# SCH.net
KiCad netlist of a schematic drawn in Altium Designer
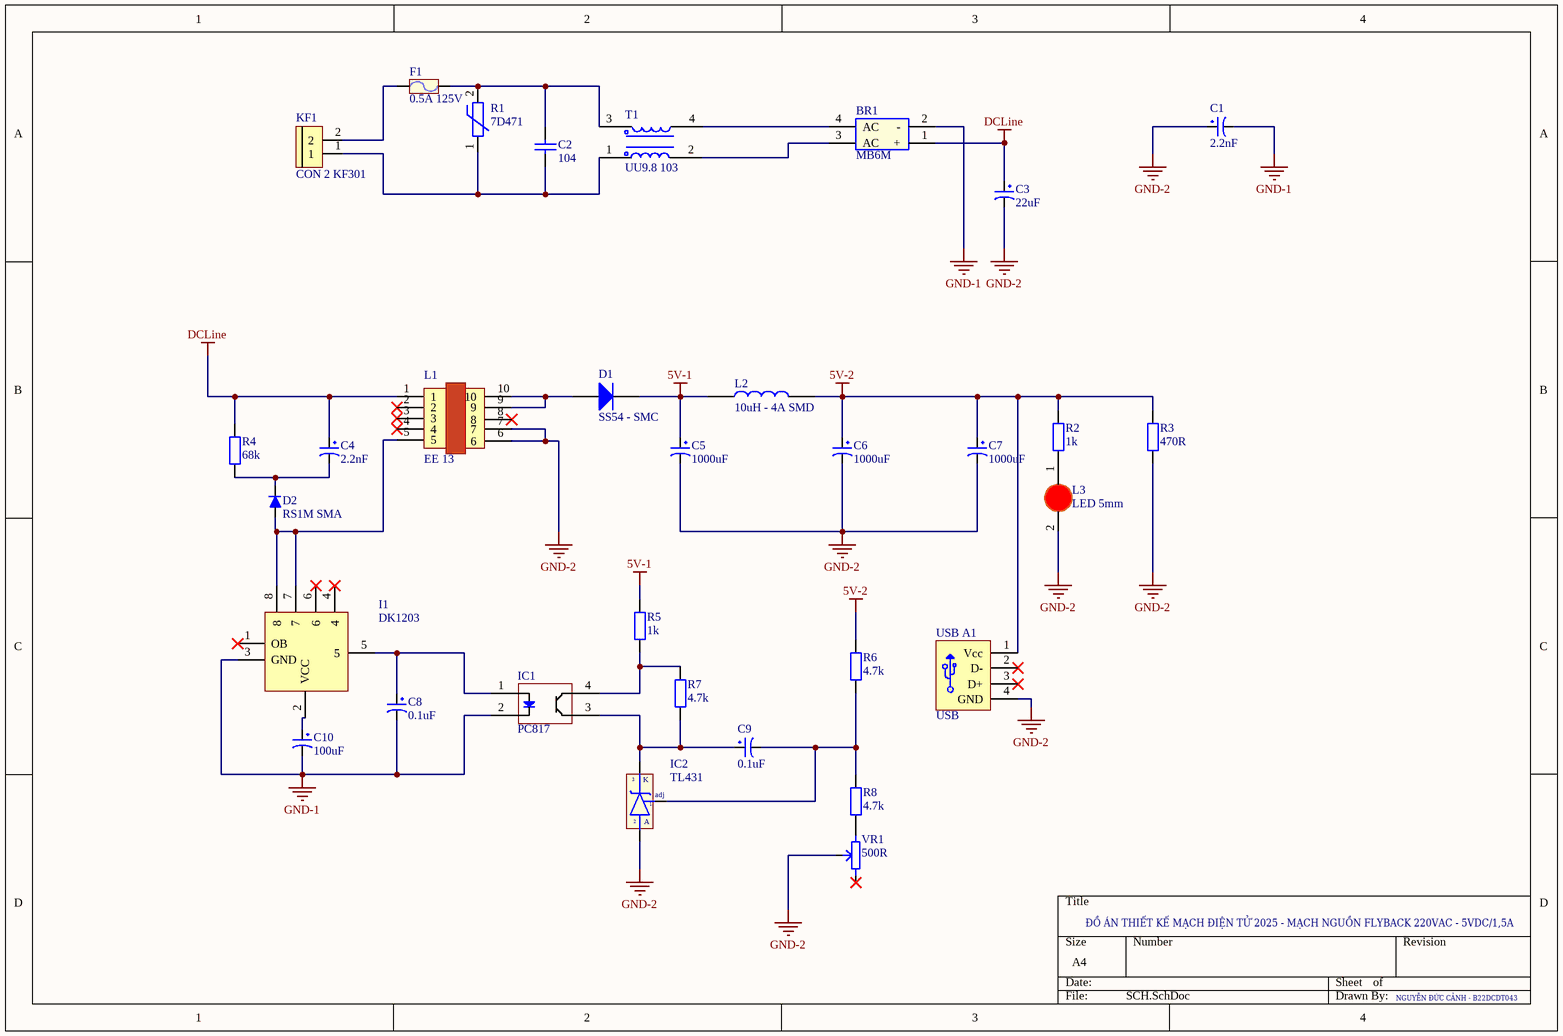
[diagram p0: SCH.SchDoc]

(export (version "E")
  (design (tool "Eeschema 10.0.6"))
  (components
    (comp (ref "BR1") (value "MB6M") (footprint "MB6M") (libsource (lib "ALLLib") (part "MB6M")))
    (comp (ref "C1")
      (value "2.2nF")
      (footprint "tu hoa 8mm")
      (description "Cắm")
      (libsource (lib "") (part "Tu Hoa 2.2uF 400V 8x12_1"))
    )
    (comp (ref "C2")
      (value "104")
      (footprint "tu gom")
      (description "Cắm")
      (libsource (lib "OCVITTV") (part "Tu gom 104 50V"))
    )
    (comp (ref "C3")
      (value "22uF")
      (footprint "tu hoa 13mm")
      (description "Cắm")
      (libsource (lib "OCVITTV") (part "Tu Hoa 22uF 400V 13x20"))
    )
    (comp (ref "C4")
      (value "2.2nF")
      (footprint "tu hoa 8mm")
      (description "Cắm")
      (libsource (lib "OCVITTV") (part "Tu Hoa 2.2uF 400V 8x12"))
    )
    (comp (ref "C5")
      (value "1000uF")
      (footprint "tu hoa 10mm")
      (description "Cắm")
      (libsource (lib "OCVITTV") (part "Tu Hoa 1000uF 10V 10x12"))
    )
    (comp (ref "C6")
      (value "1000uF")
      (footprint "tu hoa 10mm")
      (description "Cắm")
      (libsource (lib "OCVITTV") (part "Tu Hoa 1000uF 10V 10x12"))
    )
    (comp (ref "C7")
      (value "1000uF")
      (footprint "tu hoa 10mm")
      (description "Cắm")
      (libsource (lib "OCVITTV") (part "Tu Hoa 1000uF 10V 10x12"))
    )
    (comp (ref "C8")
      (value "0.1uF")
      (footprint "tu hoa 5mm")
      (description "Cắm")
      (libsource (lib "OCVITTV") (part "Tu Hoa 0.1uF 50V 5x11"))
    )
    (comp (ref "C9")
      (value "0.1uF")
      (footprint "tu hoa 5mm")
      (description "Cắm")
      (libsource (lib "") (part "Tu Hoa 0.1uF 50V 5x11_1"))
    )
    (comp (ref "C10")
      (value "100uF")
      (footprint "tu hoa 5mm")
      (description "Cắm")
      (libsource (lib "OCVITTV") (part "Tu Hoa 100uF 16V 5x7"))
    )
    (comp (ref "D1")
      (value "SS54 - SMC")
      (footprint "DIODE SMA")
      (description "Dán")
      (libsource (lib "OCVITTV") (part "Diode SS34 ( 1N5822 )"))
    )
    (comp (ref "D2") (value "RS1M SMA") (footprint "RS1M SMA") (libsource (lib "ALLLib") (part "RS1M SMA")))
    (comp (ref "F1")
      (value "0.5A 125V")
      (footprint "Cau Chi SMD1808")
      (description "Cau chi 0.5A 125V SMD1808")
      (libsource (lib "OCVITTV") (part "Cau chi 0.5A 125V SMD1808"))
    )
    (comp (ref "I1") (value "DK1203") (footprint "DK1203") (libsource (lib "ALLLib") (part "Dk1203")))
    (comp (ref "IC1") (value "PC817") (footprint "PC817") (libsource (lib "ALLLib") (part "PC871")))
    (comp (ref "IC2")
      (value "TL431")
      (footprint "qto-92")
      (description "Programmable Shunt Regulator")
      (libsource (lib "my Library") (part "TL431"))
    )
    (comp (ref "KF1")
      (value "CON 2 KF301")
      (footprint "Con 2 KF301 5.08")
      (description "Cắm")
      (libsource (lib "OCVITTV") (part "CON 2 KF301"))
    )
    (comp (ref "L1") (value "EE 13") (footprint "Trans EE13") (libsource (lib "ALLLib") (part "EE 20-10-6")))
    (comp (ref "L2")
      (value "10uH - 4A SMD")
      (footprint "Cuon Cam 7x7x5")
      (description "Dán")
      (libsource (lib "OCVITTV") (part "CUON CAM 47uH SMD"))
    )
    (comp (ref "L3")
      (value "LED 5mm")
      (footprint "LED-5MM-RED")
      (description "Cắm")
      (libsource (lib "OCVITTV") (part "LED 5mm Do"))
    )
    (comp (ref "R1")
      (value "7D471")
      (footprint "Inrush current limiter")
      (libsource (lib "ALLLib") (part "Tu chong set"))
    )
    (comp (ref "R2")
      (value "1k")
      (footprint "tro vach 1/4w")
      (description "Cắm")
      (libsource (lib "OCVITTV") (part "Tro Vach 1/4W 5% 1k"))
    )
    (comp (ref "R3")
      (value "470R")
      (footprint "tro vach 1/2w")
      (description "Cắm")
      (libsource (lib "OCVITTV") (part "Tro Vach 1/2W 5% 470R"))
    )
    (comp (ref "R4")
      (value "68k")
      (footprint "tro vach 1/4w")
      (description "Cắm")
      (libsource (lib "OCVITTV") (part "Tro Vach 1/4W 5% 68k"))
    )
    (comp (ref "R5")
      (value "1k")
      (footprint "tro vach 1/4w")
      (description "Cắm")
      (libsource (lib "OCVITTV") (part "Tro Vach 1/4W 5% 1k"))
    )
    (comp (ref "R6")
      (value "4.7k")
      (footprint "tro vach 1/4w")
      (description "Cắm")
      (libsource (lib "OCVITTV") (part "Tro Vach 1/4W 5% 4.7k"))
    )
    (comp (ref "R7")
      (value "4.7k")
      (footprint "tro vach 1/4w")
      (description "Cắm")
      (libsource (lib "OCVITTV") (part "Tro Vach 1/4W 5% 4.7k"))
    )
    (comp (ref "R8")
      (value "4.7k")
      (footprint "tro vach 1/4w")
      (description "Cắm")
      (libsource (lib "OCVITTV") (part "Tro Vach 1/4W 5% 4.7k"))
    )
    (comp (ref "T1")
      (value "UU9.8 103")
      (footprint "UU8.9 103")
      (libsource (lib "ALLLib") (part "UU9.8 103"))
    )
    (comp (ref "USB A1")
      (value "USB")
      (footprint "USB A")
      (libsource (lib "ALLLib") (part "USB TYPE A FEMALE"))
    )
    (comp (ref "VR1")
      (value "500R")
      (footprint "Bien Tro Tam Giac Dung")
      (description "Cắm")
      (libsource (lib "OCVITTV") (part "Bien tro tam giac 1K Dung"))
    )
  )
  (nets
    (net (code "1") (name "5V-1") (class "Default")
      (node (ref "C5") (pin "1") (pinfunction "1_1") (pintype "passive"))
      (node (ref "D1") (pin "2") (pinfunction "K_2") (pintype "passive"))
      (node (ref "L2") (pin "1") (pinfunction "1_1") (pintype "passive"))
      (node (ref "R5") (pin "2") (pinfunction "2_2") (pintype "passive"))
    )
    (net (code "2") (name "5V-2") (class "Default")
      (node (ref "C6") (pin "1") (pinfunction "1_1") (pintype "passive"))
      (node (ref "C7") (pin "1") (pinfunction "1_1") (pintype "passive"))
      (node (ref "L2") (pin "2") (pinfunction "2_2") (pintype "passive"))
      (node (ref "R2") (pin "2") (pinfunction "2_2") (pintype "passive"))
      (node (ref "R3") (pin "2") (pinfunction "2_2") (pintype "passive"))
      (node (ref "R6") (pin "2") (pinfunction "2_2") (pintype "passive"))
      (node (ref "USB A1") (pin "1") (pinfunction "Vcc_1") (pintype "passive"))
    )
    (net (code "3") (name "DCLine") (class "Default")
      (node (ref "BR1") (pin "1") (pinfunction "+_1") (pintype "passive"))
      (node (ref "C3") (pin "1") (pinfunction "1_1") (pintype "passive"))
      (node (ref "C4") (pin "1") (pinfunction "1_1") (pintype "passive"))
      (node (ref "L1") (pin "1") (pinfunction "1_1") (pintype "passive"))
      (node (ref "R4") (pin "2") (pinfunction "2_2") (pintype "passive"))
    )
    (net (code "4") (name "GND-1") (class "Default")
      (node (ref "BR1") (pin "2") (pinfunction "-_2") (pintype "passive"))
      (node (ref "C1") (pin "2") (pinfunction "2_2") (pintype "passive"))
      (node (ref "C10") (pin "2") (pinfunction "2_2") (pintype "passive"))
      (node (ref "C8") (pin "2") (pinfunction "2_2") (pintype "passive"))
      (node (ref "I1") (pin "3") (pinfunction "GND_3") (pintype "passive"))
      (node (ref "IC1") (pin "2") (pinfunction "2_2") (pintype "passive"))
    )
    (net (code "5") (name "GND-2") (class "Default")
      (node (ref "C1") (pin "1") (pinfunction "1_1") (pintype "passive"))
      (node (ref "C3") (pin "2") (pinfunction "2_2") (pintype "passive"))
      (node (ref "C5") (pin "2") (pinfunction "2_2") (pintype "passive"))
      (node (ref "C6") (pin "2") (pinfunction "2_2") (pintype "passive"))
      (node (ref "C7") (pin "2") (pinfunction "2_2") (pintype "passive"))
      (node (ref "IC2") (pin "2") (pinfunction "A_2") (pintype "passive"))
      (node (ref "L1") (pin "6") (pinfunction "6_6") (pintype "passive"))
      (node (ref "L1") (pin "7") (pinfunction "7_7") (pintype "passive"))
      (node (ref "L3") (pin "2") (pinfunction "K_2") (pintype "passive"))
      (node (ref "R3") (pin "1") (pinfunction "1_1") (pintype "passive"))
      (node (ref "USB A1") (pin "4") (pinfunction "GND_4") (pintype "passive"))
      (node (ref "VR1") (pin "2") (pinfunction "2_2") (pintype "passive"))
    )
    (net (code "6") (name "Net-(BR1-AC-Pad3)") (class "Default")
      (node (ref "BR1") (pin "3") (pinfunction "AC_3") (pintype "passive"))
      (node (ref "T1") (pin "2") (pinfunction "2_2") (pintype "passive"))
    )
    (net (code "7") (name "Net-(BR1-AC-Pad4)") (class "Default")
      (node (ref "BR1") (pin "4") (pinfunction "AC_4") (pintype "passive"))
      (node (ref "T1") (pin "4") (pinfunction "4_4") (pintype "passive"))
    )
    (net (code "8") (name "Net-(C2-Pad1)") (class "Default")
      (node (ref "C2") (pin "1") (pinfunction "1_1") (pintype "passive"))
      (node (ref "F1") (pin "2") (pinfunction "2_2") (pintype "passive"))
      (node (ref "R1") (pin "2") (pinfunction "2_2") (pintype "passive"))
      (node (ref "T1") (pin "3") (pinfunction "3_3") (pintype "passive"))
    )
    (net (code "9") (name "Net-(C2-Pad2)") (class "Default")
      (node (ref "C2") (pin "2") (pinfunction "2_2") (pintype "passive"))
      (node (ref "KF1") (pin "1") (pinfunction "1_1") (pintype "passive"))
      (node (ref "R1") (pin "1") (pinfunction "1_1") (pintype "passive"))
      (node (ref "T1") (pin "1") (pinfunction "1_1") (pintype "passive"))
    )
    (net (code "10") (name "Net-(C4-Pad2)") (class "Default")
      (node (ref "C4") (pin "2") (pinfunction "2_2") (pintype "passive"))
      (node (ref "D2") (pin "1") (pinfunction "1_1") (pintype "passive"))
      (node (ref "R4") (pin "1") (pinfunction "1_1") (pintype "passive"))
    )
    (net (code "11") (name "Net-(C8-Pad1)") (class "Default")
      (node (ref "C8") (pin "1") (pinfunction "1_1") (pintype "passive"))
      (node (ref "I1") (pin "5") (pinfunction "5_5") (pintype "passive"))
      (node (ref "IC1") (pin "1") (pinfunction "1_1") (pintype "passive"))
    )
    (net (code "12") (name "Net-(D1-A)") (class "Default")
      (node (ref "D1") (pin "1") (pinfunction "A_1") (pintype "passive"))
      (node (ref "L1") (pin "10") (pinfunction "10_10") (pintype "passive"))
      (node (ref "L1") (pin "9") (pinfunction "9_9") (pintype "passive"))
    )
    (net (code "13") (name "Net-(D2-Pad2)") (class "Default")
      (node (ref "D2") (pin "2") (pinfunction "2_2") (pintype "passive"))
      (node (ref "I1") (pin "7") (pinfunction "7_7") (pintype "passive"))
      (node (ref "I1") (pin "8") (pinfunction "8_8") (pintype "passive"))
      (node (ref "L1") (pin "5") (pinfunction "5_5") (pintype "passive"))
    )
    (net (code "14") (name "Net-(F1-Pad1)") (class "Default")
      (node (ref "F1") (pin "1") (pinfunction "1_1") (pintype "passive"))
      (node (ref "KF1") (pin "2") (pinfunction "2_2") (pintype "passive"))
    )
    (net (code "15") (name "Net-(I1-VCC)") (class "Default")
      (node (ref "C10") (pin "1") (pinfunction "1_1") (pintype "passive"))
      (node (ref "I1") (pin "2") (pinfunction "VCC_2") (pintype "passive"))
    )
    (net (code "16") (name "Net-(IC1-Pad4)") (class "Default")
      (node (ref "IC1") (pin "4") (pinfunction "4_4") (pintype "passive"))
      (node (ref "R5") (pin "1") (pinfunction "1_1") (pintype "passive"))
      (node (ref "R7") (pin "2") (pinfunction "2_2") (pintype "passive"))
    )
    (net (code "17") (name "Net-(IC2-K)") (class "Default")
      (node (ref "C9") (pin "1") (pinfunction "1_1") (pintype "passive"))
      (node (ref "IC1") (pin "3") (pinfunction "3_3") (pintype "passive"))
      (node (ref "IC2") (pin "3") (pinfunction "K_3") (pintype "passive"))
      (node (ref "R7") (pin "1") (pinfunction "1_1") (pintype "passive"))
    )
    (net (code "18") (name "Net-(IC2-adj)") (class "Default")
      (node (ref "C9") (pin "2") (pinfunction "2_2") (pintype "passive"))
      (node (ref "IC2") (pin "1") (pinfunction "adj_1") (pintype "passive"))
      (node (ref "R6") (pin "1") (pinfunction "1_1") (pintype "passive"))
      (node (ref "R8") (pin "2") (pinfunction "2_2") (pintype "passive"))
    )
    (net (code "19") (name "Net-(L3-A)") (class "Default")
      (node (ref "L3") (pin "1") (pinfunction "A_1") (pintype "passive"))
      (node (ref "R2") (pin "1") (pinfunction "1_1") (pintype "passive"))
    )
    (net (code "20") (name "Net-(R8-Pad1)") (class "Default")
      (node (ref "R8") (pin "1") (pinfunction "1_1") (pintype "passive"))
      (node (ref "VR1") (pin "3") (pinfunction "3_3") (pintype "passive"))
    )
    (net (code "21") (name "unconnected-(I1-OB-Pad1)") (class "Default")
      (node (ref "I1") (pin "1") (pinfunction "OB_1") (pintype "passive+no_connect"))
    )
    (net (code "22") (name "unconnected-(I1-Pad4)") (class "Default")
      (node (ref "I1") (pin "4") (pinfunction "4_4") (pintype "passive+no_connect"))
    )
    (net (code "23") (name "unconnected-(I1-Pad6)") (class "Default")
      (node (ref "I1") (pin "6") (pinfunction "6_6") (pintype "passive+no_connect"))
    )
    (net (code "24") (name "unconnected-(L1-Pad2)") (class "Default")
      (node (ref "L1") (pin "2") (pinfunction "2_2") (pintype "passive+no_connect"))
    )
    (net (code "25") (name "unconnected-(L1-Pad3)") (class "Default")
      (node (ref "L1") (pin "3") (pinfunction "3_3") (pintype "passive+no_connect"))
    )
    (net (code "26") (name "unconnected-(L1-Pad4)") (class "Default")
      (node (ref "L1") (pin "4") (pinfunction "4_4") (pintype "passive+no_connect"))
    )
    (net (code "27") (name "unconnected-(L1-Pad8)") (class "Default")
      (node (ref "L1") (pin "8") (pinfunction "8_8") (pintype "passive+no_connect"))
    )
    (net (code "28") (name "unconnected-(USB A1-D+-Pad3)") (class "Default")
      (node (ref "USB A1") (pin "3") (pinfunction "D+_3") (pintype "passive+no_connect"))
    )
    (net (code "29") (name "unconnected-(USB A1-D--Pad2)") (class "Default")
      (node (ref "USB A1") (pin "2") (pinfunction "D-_2") (pintype "passive+no_connect"))
    )
    (net (code "30") (name "unconnected-(VR1-Pad1)") (class "Default")
      (node (ref "VR1") (pin "1") (pinfunction "1_1") (pintype "passive+no_connect"))
    )
  )
)
